# relayProtoType.net
KiCad netlist of a schematic drawn in EAGLE
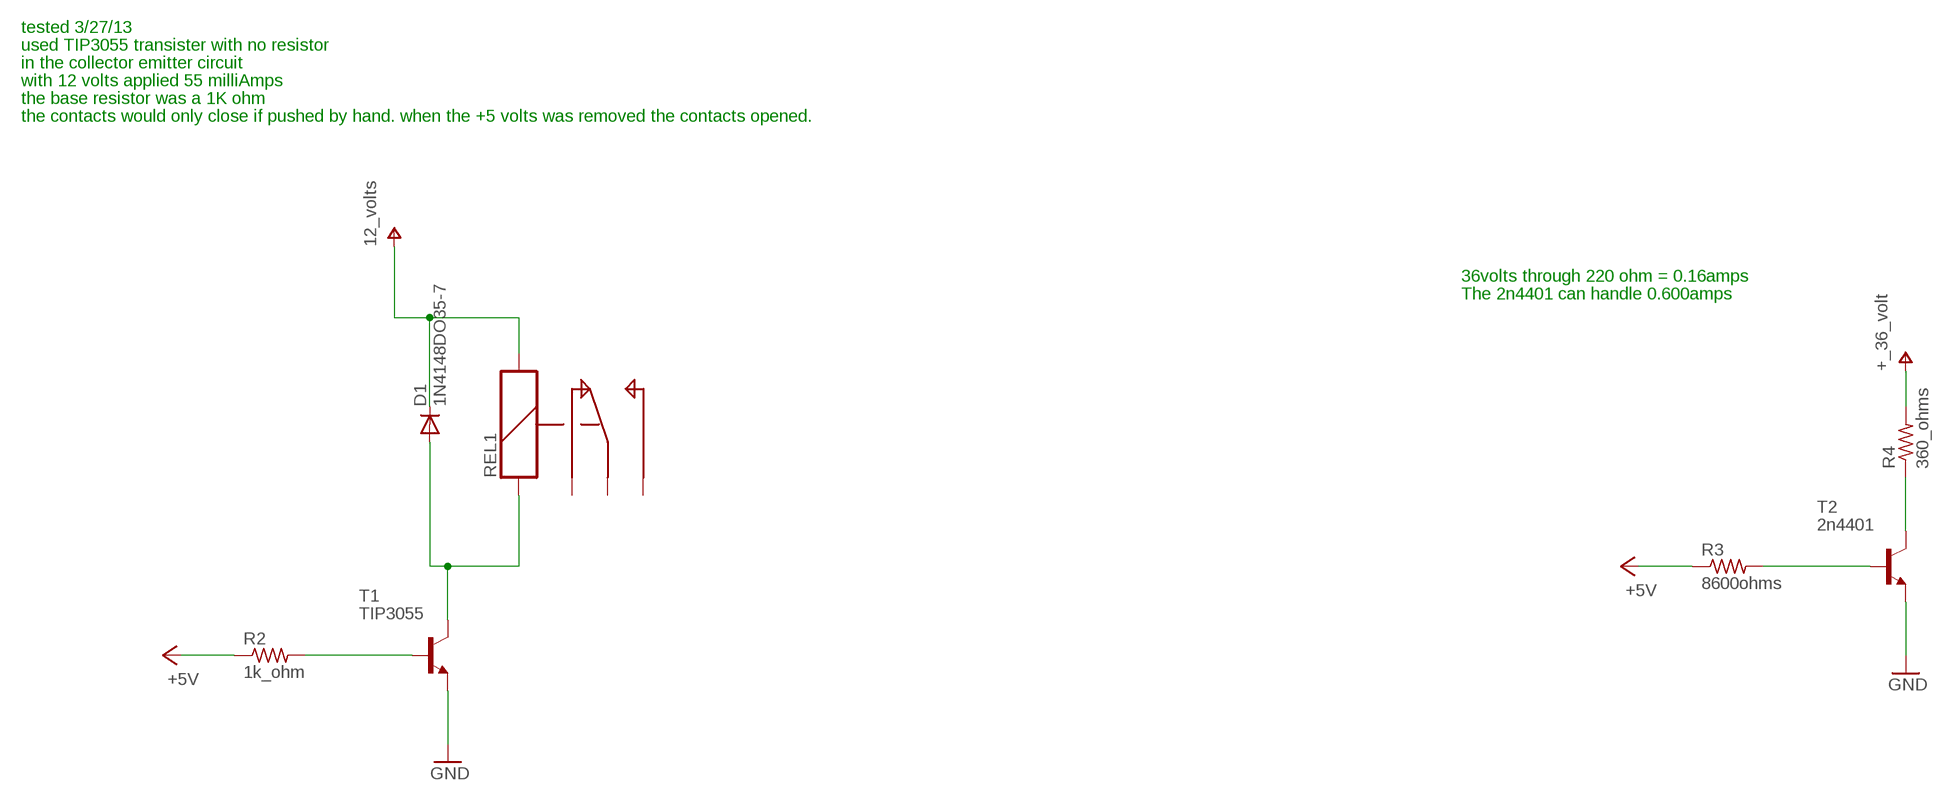
[diagram p0: schematic, sheet 1]

(export (version "E")
  (design (tool "Eeschema 10.0.6"))
  (components
    (comp (ref "D1")
      (value "1N4148DO35-7")
      (footprint "eagle-import:DO35-7")
      (libsource (lib "eagle-import") (part "1N4148DO35-7"))
    )
    (comp (ref "R2")
      (value "1k_ohm")
      (footprint "eagle-import:0207_10")
      (libsource (lib "eagle-import") (part "R-US_0207/10"))
    )
    (comp (ref "R3")
      (value "8600ohms")
      (footprint "eagle-import:0207_10")
      (libsource (lib "eagle-import") (part "R-US_0207/10"))
    )
    (comp (ref "R4")
      (value "360_ohms")
      (footprint "eagle-import:0207_10")
      (libsource (lib "eagle-import") (part "R-US_0207/10"))
    )
    (comp (ref "REL1")
      (value "REL-5PIN")
      (footprint "eagle-import:REL-5PIN")
      (libsource (lib "eagle-import") (part "REL-5PIN"))
    )
    (comp (ref "T1")
      (value "TIP3055")
      (footprint "eagle-import:TO92")
      (libsource (lib "eagle-import") (part "-NPN-TO92"))
    )
    (comp (ref "T2")
      (value "2n4401")
      (footprint "eagle-import:TO92")
      (libsource (lib "eagle-import") (part "-NPN-TO92"))
    )
  )
  (nets
    (net (code "1") (name "+5V") (class "Default")
      (node (ref "R2") (pin "1") (pinfunction "1_1") (pintype "passive"))
      (node (ref "R3") (pin "1") (pinfunction "1_1") (pintype "passive"))
    )
    (net (code "2") (name "+_36_volt") (class "Default")
      (node (ref "D1") (pin "C") (pinfunction "C_C") (pintype "passive"))
      (node (ref "R4") (pin "2") (pinfunction "2_2") (pintype "passive"))
      (node (ref "REL1") (pin "S2") (pinfunction "S2_S2") (pintype "passive"))
    )
    (net (code "3") (name "GND") (class "Default")
      (node (ref "T1") (pin "1") (pinfunction "E_1") (pintype "passive"))
      (node (ref "T2") (pin "1") (pinfunction "E_1") (pintype "passive"))
    )
    (net (code "4") (name "Net-(T1-B)") (class "Default")
      (node (ref "R2") (pin "2") (pinfunction "2_2") (pintype "passive"))
      (node (ref "T1") (pin "2") (pinfunction "B_2") (pintype "passive"))
    )
    (net (code "5") (name "Net-(T1-C)") (class "Default")
      (node (ref "D1") (pin "A") (pinfunction "A_A") (pintype "passive"))
      (node (ref "REL1") (pin "S1") (pinfunction "S1_S1") (pintype "passive"))
      (node (ref "T1") (pin "3") (pinfunction "C_3") (pintype "passive"))
    )
    (net (code "6") (name "Net-(T2-B)") (class "Default")
      (node (ref "R3") (pin "2") (pinfunction "2_2") (pintype "passive"))
      (node (ref "T2") (pin "2") (pinfunction "B_2") (pintype "passive"))
    )
    (net (code "7") (name "Net-(T2-C)") (class "Default")
      (node (ref "R4") (pin "1") (pinfunction "1_1") (pintype "passive"))
      (node (ref "T2") (pin "3") (pinfunction "C_3") (pintype "passive"))
    )
    (net (code "8") (name "unconnected-(REL1-PadC)") (class "Default")
      (node (ref "REL1") (pin "C") (pinfunction "C_C") (pintype "passive"))
    )
    (net (code "9") (name "unconnected-(REL1-PadO)") (class "Default")
      (node (ref "REL1") (pin "O") (pinfunction "O_O") (pintype "passive"))
    )
    (net (code "10") (name "unconnected-(REL1-PadS)") (class "Default")
      (node (ref "REL1") (pin "S") (pinfunction "S_S") (pintype "passive"))
    )
  )
)
